# LED-Lampe_Power_ZXLD1362.net
KiCad netlist of a schematic drawn in EAGLE
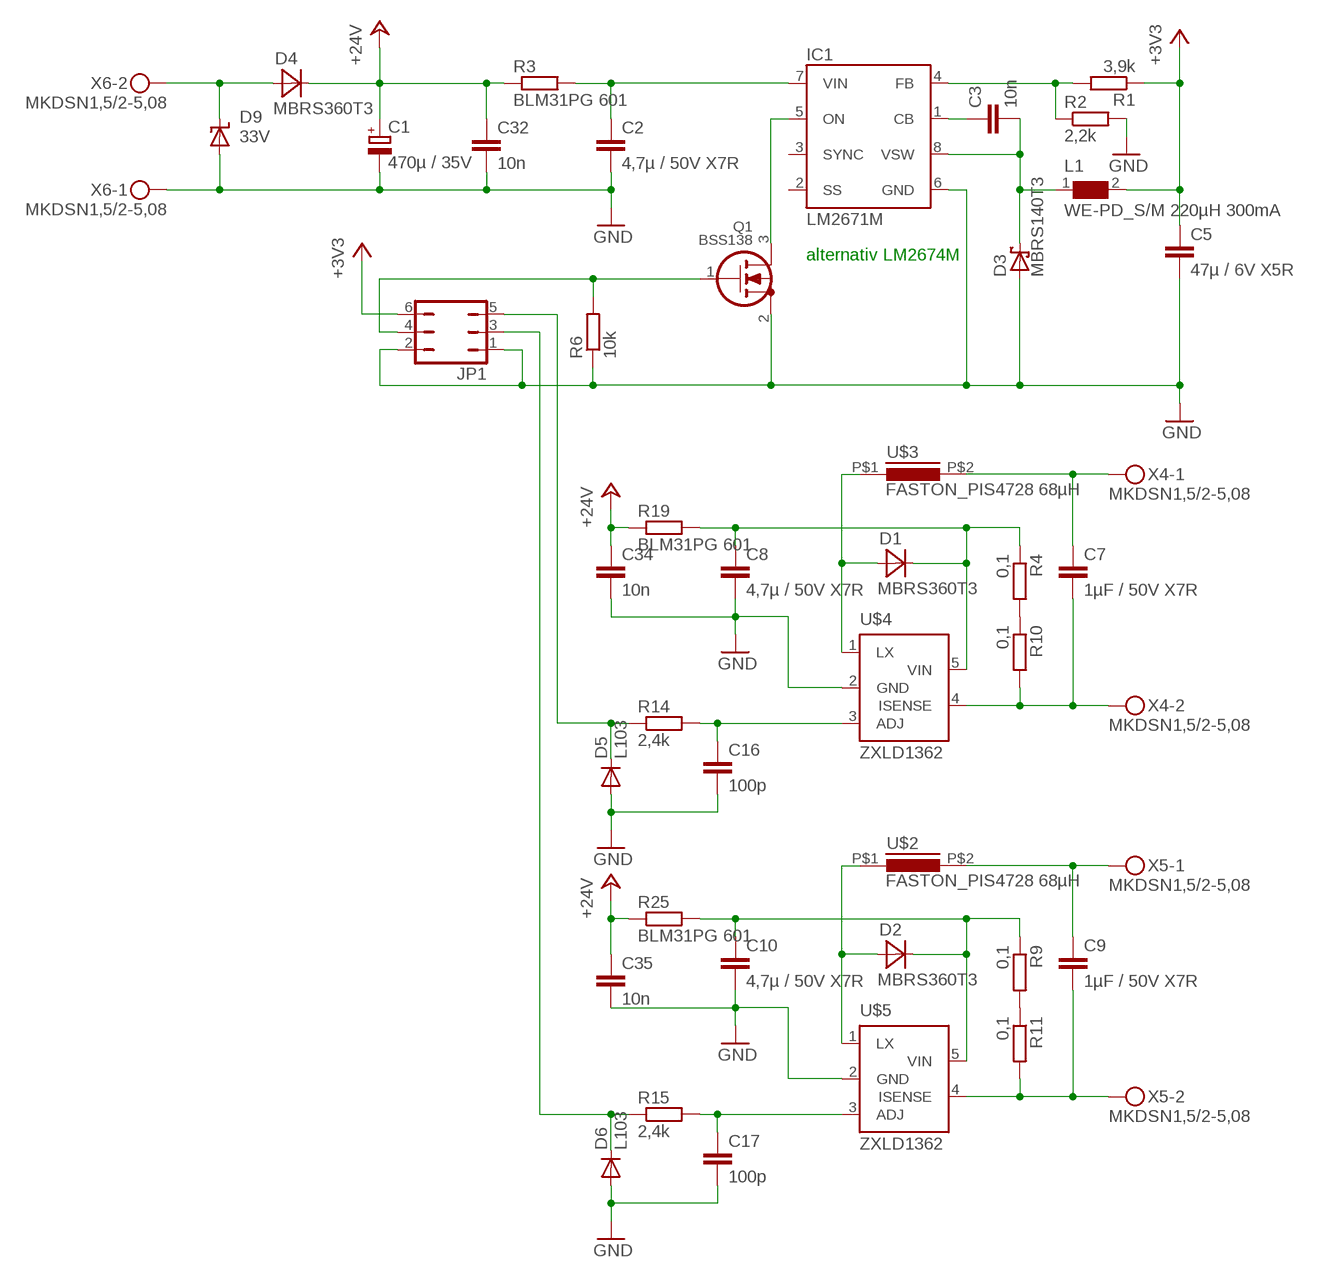
[diagram p0: schematic, sheet 1]

(export (version "E")
  (design (tool "Eeschema 10.0.6"))
  (components
    (comp (ref "C1")
      (value "470µ / 35V")
      (footprint "eagle-import:E5-13")
      (libsource (lib "eagle-import") (part "CPOL-EUE5-13"))
    )
    (comp (ref "C2")
      (value "4,7µ / 50V X7R")
      (footprint "eagle-import:C1206")
      (libsource (lib "eagle-import") (part "resistor_C-EUC1206"))
    )
    (comp (ref "C3")
      (value "10n")
      (footprint "eagle-import:C1206")
      (libsource (lib "eagle-import") (part "C-EUC1206"))
    )
    (comp (ref "C5")
      (value "47µ / 6V X5R")
      (footprint "eagle-import:C1206")
      (libsource (lib "eagle-import") (part "resistor_C-EUC1206"))
    )
    (comp (ref "C7")
      (value "1µF / 50V X7R")
      (footprint "eagle-import:C1206")
      (libsource (lib "eagle-import") (part "resistor_C-EUC1206"))
    )
    (comp (ref "C8")
      (value "4,7µ / 50V X7R")
      (footprint "eagle-import:C1206")
      (libsource (lib "eagle-import") (part "resistor_C-EUC1206"))
    )
    (comp (ref "C9")
      (value "1µF / 50V X7R")
      (footprint "eagle-import:C1206")
      (libsource (lib "eagle-import") (part "resistor_C-EUC1206"))
    )
    (comp (ref "C10")
      (value "4,7µ / 50V X7R")
      (footprint "eagle-import:C1206")
      (libsource (lib "eagle-import") (part "resistor_C-EUC1206"))
    )
    (comp (ref "C16")
      (value "100p")
      (footprint "eagle-import:C0603")
      (libsource (lib "eagle-import") (part "C-EUC0603"))
    )
    (comp (ref "C17")
      (value "100p")
      (footprint "eagle-import:C0603")
      (libsource (lib "eagle-import") (part "C-EUC0603"))
    )
    (comp (ref "C32")
      (value "10n")
      (footprint "eagle-import:C1206")
      (libsource (lib "eagle-import") (part "C-EUC1206"))
    )
    (comp (ref "C34")
      (value "10n")
      (footprint "eagle-import:C1206")
      (libsource (lib "eagle-import") (part "C-EUC1206"))
    )
    (comp (ref "C35")
      (value "10n")
      (footprint "eagle-import:C1206")
      (libsource (lib "eagle-import") (part "C-EUC1206"))
    )
    (comp (ref "D1")
      (value "MBRS360T3")
      (footprint "eagle-import:SMC")
      (libsource (lib "eagle-import") (part "MBRS360T3"))
    )
    (comp (ref "D2")
      (value "MBRS360T3")
      (footprint "eagle-import:SMC")
      (libsource (lib "eagle-import") (part "MBRS360T3"))
    )
    (comp (ref "D3")
      (value "MBRS140T3")
      (footprint "eagle-import:SMB")
      (libsource (lib "eagle-import") (part "SCHOTTKY-DIODESMD"))
    )
    (comp (ref "D4")
      (value "MBRS360T3")
      (footprint "eagle-import:SMC")
      (libsource (lib "eagle-import") (part "MBRS360T3"))
    )
    (comp (ref "D5")
      (value "L103")
      (footprint "eagle-import:SOD123")
      (libsource (lib "eagle-import") (part "DIODE-SOD123"))
    )
    (comp (ref "D6")
      (value "L103")
      (footprint "eagle-import:SOD123")
      (libsource (lib "eagle-import") (part "DIODE-SOD123"))
    )
    (comp (ref "D9")
      (value "33V")
      (footprint "eagle-import:SMBJ")
      (libsource (lib "eagle-import") (part "SUPPRESSOR-SMBJ"))
    )
    (comp (ref "IC1")
      (value "LM2671M")
      (footprint "eagle-import:SO08")
      (libsource (lib "eagle-import") (part "LM2671M"))
    )
    (comp (ref "JP1")
      (value "JP3Q")
      (footprint "eagle-import:JP3Q")
      (libsource (lib "eagle-import") (part "JP3Q"))
    )
    (comp (ref "L1")
      (value "WE-PD_S/M 220µH 300mA")
      (footprint "eagle-import:WE-PD_S_M")
      (libsource (lib "eagle-import") (part "WE-PD_S/M"))
    )
    (comp (ref "Q1")
      (value "BSS138")
      (footprint "eagle-import:SOT23")
      (libsource (lib "eagle-import") (part "BSS138"))
    )
    (comp (ref "R1")
      (value "3,9k")
      (footprint "eagle-import:R1206")
      (libsource (lib "eagle-import") (part "R-EU_R1206"))
    )
    (comp (ref "R2")
      (value "2,2k")
      (footprint "eagle-import:R1206")
      (libsource (lib "eagle-import") (part "R-EU_R1206"))
    )
    (comp (ref "R3")
      (value "BLM31PG 601")
      (footprint "eagle-import:R1206@1")
      (libsource (lib "eagle-import") (part "resistor_R-EU_R1206"))
    )
    (comp (ref "R4")
      (value "0,1")
      (footprint "eagle-import:R1206@1")
      (libsource (lib "eagle-import") (part "resistor_R-EU_R1206"))
    )
    (comp (ref "R6")
      (value "10k")
      (footprint "eagle-import:R1206")
      (libsource (lib "eagle-import") (part "R-EU_R1206"))
    )
    (comp (ref "R9")
      (value "0,1")
      (footprint "eagle-import:R1206@1")
      (libsource (lib "eagle-import") (part "resistor_R-EU_R1206"))
    )
    (comp (ref "R10")
      (value "0,1")
      (footprint "eagle-import:R1206@1")
      (libsource (lib "eagle-import") (part "resistor_R-EU_R1206"))
    )
    (comp (ref "R11")
      (value "0,1")
      (footprint "eagle-import:R1206@1")
      (libsource (lib "eagle-import") (part "resistor_R-EU_R1206"))
    )
    (comp (ref "R14")
      (value "2,4k")
      (footprint "eagle-import:R1206")
      (libsource (lib "eagle-import") (part "R-EU_R1206"))
    )
    (comp (ref "R15")
      (value "2,4k")
      (footprint "eagle-import:R1206")
      (libsource (lib "eagle-import") (part "R-EU_R1206"))
    )
    (comp (ref "R19")
      (value "BLM31PG 601")
      (footprint "eagle-import:R1206@1")
      (libsource (lib "eagle-import") (part "resistor_R-EU_R1206"))
    )
    (comp (ref "R25")
      (value "BLM31PG 601")
      (footprint "eagle-import:R1206@1")
      (libsource (lib "eagle-import") (part "resistor_R-EU_R1206"))
    )
    (comp (ref "U$2")
      (value "FASTON_PIS4728 68µH")
      (footprint "eagle-import:FASTON_PIS4728")
      (libsource (lib "eagle-import") (part "FASTON_PIS4728"))
    )
    (comp (ref "U$3")
      (value "FASTON_PIS4728 68µH")
      (footprint "eagle-import:FASTON_PIS4728")
      (libsource (lib "eagle-import") (part "FASTON_PIS4728"))
    )
    (comp (ref "U$4")
      (value "ZXLD1362")
      (footprint "eagle-import:SOT23-5")
      (libsource (lib "eagle-import") (part "ZXLD1362"))
    )
    (comp (ref "U$5")
      (value "ZXLD1362")
      (footprint "eagle-import:SOT23-5")
      (libsource (lib "eagle-import") (part "ZXLD1362"))
    )
    (comp (ref "X4")
      (value "MKDSN1,5/2-5,08")
      (footprint "eagle-import:MKDSN1,5_2-5,08")
      (fields (field (name "MPN") "MKDSN 1,5/2-5.08"))
      (libsource (lib "eagle-import") (part "MKDSN1,5/2-5,08"))
    )
    (comp (ref "X5")
      (value "MKDSN1,5/2-5,08")
      (footprint "eagle-import:MKDSN1,5_2-5,08")
      (fields (field (name "MPN") "MKDSN 1,5/2-5.08"))
      (libsource (lib "eagle-import") (part "MKDSN1,5/2-5,08"))
    )
    (comp (ref "X6")
      (value "MKDSN1,5/2-5,08")
      (footprint "eagle-import:MKDSN1,5_2-5,08")
      (fields (field (name "MPN") "MKDSN 1,5/2-5.08"))
      (libsource (lib "eagle-import") (part "MKDSN1,5/2-5,08"))
    )
  )
  (nets
    (net (code "1") (name "+3V3") (class "Default")
      (node (ref "C5") (pin "1") (pinfunction "1_1") (pintype "passive"))
      (node (ref "JP1") (pin "6") (pinfunction "6_6") (pintype "passive"))
      (node (ref "L1") (pin "2") (pinfunction "2_2") (pintype "passive"))
      (node (ref "R1") (pin "1") (pinfunction "1_1") (pintype "passive"))
    )
    (net (code "2") (name "+24V") (class "Default")
      (node (ref "C1") (pin "+") (pinfunction "+_+") (pintype "passive"))
      (node (ref "C32") (pin "1") (pinfunction "1_1") (pintype "passive"))
      (node (ref "C34") (pin "1") (pinfunction "1_1") (pintype "passive"))
      (node (ref "C35") (pin "1") (pinfunction "1_1") (pintype "passive"))
      (node (ref "D4") (pin "C") (pinfunction "C_C") (pintype "passive"))
      (node (ref "R19") (pin "1") (pinfunction "1_1") (pintype "passive"))
      (node (ref "R25") (pin "1") (pinfunction "1_1") (pintype "passive"))
      (node (ref "R3") (pin "1") (pinfunction "1_1") (pintype "passive"))
    )
    (net (code "3") (name "GND") (class "Default")
      (node (ref "C1") (pin "-") (pinfunction "-_-") (pintype "passive"))
      (node (ref "C10") (pin "2") (pinfunction "2_2") (pintype "passive"))
      (node (ref "C16") (pin "2") (pinfunction "2_2") (pintype "passive"))
      (node (ref "C17") (pin "2") (pinfunction "2_2") (pintype "passive"))
      (node (ref "C2") (pin "2") (pinfunction "2_2") (pintype "passive"))
      (node (ref "C32") (pin "2") (pinfunction "2_2") (pintype "passive"))
      (node (ref "C34") (pin "2") (pinfunction "2_2") (pintype "passive"))
      (node (ref "C35") (pin "2") (pinfunction "2_2") (pintype "passive"))
      (node (ref "C5") (pin "2") (pinfunction "2_2") (pintype "passive"))
      (node (ref "C8") (pin "2") (pinfunction "2_2") (pintype "passive"))
      (node (ref "D3") (pin "A") (pinfunction "A_A") (pintype "passive"))
      (node (ref "D5") (pin "A") (pinfunction "A_A") (pintype "passive"))
      (node (ref "D6") (pin "A") (pinfunction "A_A") (pintype "passive"))
      (node (ref "D9") (pin "A") (pinfunction "A_A") (pintype "passive"))
      (node (ref "IC1") (pin "6") (pinfunction "GND_6") (pintype "power_in"))
      (node (ref "JP1") (pin "1") (pinfunction "1_1") (pintype "passive"))
      (node (ref "JP1") (pin "2") (pinfunction "2_2") (pintype "passive"))
      (node (ref "Q1") (pin "2") (pinfunction "S_2") (pintype "bidirectional"))
      (node (ref "R2") (pin "2") (pinfunction "2_2") (pintype "passive"))
      (node (ref "R6") (pin "1") (pinfunction "1_1") (pintype "passive"))
      (node (ref "U$4") (pin "2") (pinfunction "GND_2") (pintype "power_in"))
      (node (ref "U$5") (pin "2") (pinfunction "GND_2") (pintype "power_in"))
      (node (ref "X6") (pin "1") (pinfunction "KL_1") (pintype "passive"))
    )
    (net (code "4") (name "Net-(D5-PadC)") (class "Default")
      (node (ref "D5") (pin "C") (pinfunction "C_C") (pintype "passive"))
      (node (ref "JP1") (pin "5") (pinfunction "5_5") (pintype "passive"))
      (node (ref "R14") (pin "1") (pinfunction "1_1") (pintype "passive"))
    )
    (net (code "5") (name "Net-(D6-PadC)") (class "Default")
      (node (ref "D6") (pin "C") (pinfunction "C_C") (pintype "passive"))
      (node (ref "JP1") (pin "3") (pinfunction "3_3") (pintype "passive"))
      (node (ref "R15") (pin "1") (pinfunction "1_1") (pintype "passive"))
    )
    (net (code "6") (name "Net-(IC1-CB)") (class "Default")
      (node (ref "C3") (pin "1") (pinfunction "1_1") (pintype "passive"))
      (node (ref "IC1") (pin "1") (pinfunction "CB_1") (pintype "input"))
    )
    (net (code "7") (name "Net-(IC1-FB)") (class "Default")
      (node (ref "IC1") (pin "4") (pinfunction "FB_4") (pintype "input"))
      (node (ref "R1") (pin "2") (pinfunction "2_2") (pintype "passive"))
      (node (ref "R2") (pin "1") (pinfunction "1_1") (pintype "passive"))
    )
    (net (code "8") (name "Net-(IC1-ON)") (class "Default")
      (node (ref "IC1") (pin "5") (pinfunction "ON_5") (pintype "passive"))
      (node (ref "Q1") (pin "3") (pinfunction "D_3") (pintype "bidirectional"))
    )
    (net (code "9") (name "Net-(IC1-VIN)") (class "Default")
      (node (ref "C2") (pin "1") (pinfunction "1_1") (pintype "passive"))
      (node (ref "IC1") (pin "7") (pinfunction "VIN_7") (pintype "power_in"))
      (node (ref "R3") (pin "2") (pinfunction "2_2") (pintype "passive"))
    )
    (net (code "10") (name "Net-(IC1-VSW)") (class "Default")
      (node (ref "C3") (pin "2") (pinfunction "2_2") (pintype "passive"))
      (node (ref "D3") (pin "C") (pinfunction "C_C") (pintype "passive"))
      (node (ref "IC1") (pin "8") (pinfunction "VSW_8") (pintype "output"))
      (node (ref "L1") (pin "1") (pinfunction "1_1") (pintype "passive"))
    )
    (net (code "11") (name "Net-(Q1-G)") (class "Default")
      (node (ref "JP1") (pin "4") (pinfunction "4_4") (pintype "passive"))
      (node (ref "Q1") (pin "1") (pinfunction "G_1") (pintype "bidirectional"))
      (node (ref "R6") (pin "2") (pinfunction "2_2") (pintype "passive"))
    )
    (net (code "12") (name "Net-(R10-Pad1)") (class "Default")
      (node (ref "R10") (pin "1") (pinfunction "1_1") (pintype "passive"))
      (node (ref "R4") (pin "2") (pinfunction "2_2") (pintype "passive"))
    )
    (net (code "13") (name "Net-(R11-Pad1)") (class "Default")
      (node (ref "R11") (pin "1") (pinfunction "1_1") (pintype "passive"))
      (node (ref "R9") (pin "2") (pinfunction "2_2") (pintype "passive"))
    )
    (net (code "14") (name "Net-(U$2-1)") (class "Default")
      (node (ref "D2") (pin "A") (pinfunction "A_A") (pintype "passive"))
      (node (ref "U$2") (pin "P$1") (pinfunction "1_P$1") (pintype "passive"))
      (node (ref "U$5") (pin "1") (pinfunction "LX_1") (pintype "output"))
    )
    (net (code "15") (name "Net-(U$2-2)") (class "Default")
      (node (ref "C9") (pin "1") (pinfunction "1_1") (pintype "passive"))
      (node (ref "U$2") (pin "P$2") (pinfunction "2_P$2") (pintype "passive"))
      (node (ref "X5") (pin "1") (pinfunction "KL_1") (pintype "passive"))
    )
    (net (code "16") (name "Net-(U$3-1)") (class "Default")
      (node (ref "D1") (pin "A") (pinfunction "A_A") (pintype "passive"))
      (node (ref "U$3") (pin "P$1") (pinfunction "1_P$1") (pintype "passive"))
      (node (ref "U$4") (pin "1") (pinfunction "LX_1") (pintype "output"))
    )
    (net (code "17") (name "Net-(U$3-2)") (class "Default")
      (node (ref "C7") (pin "1") (pinfunction "1_1") (pintype "passive"))
      (node (ref "U$3") (pin "P$2") (pinfunction "2_P$2") (pintype "passive"))
      (node (ref "X4") (pin "1") (pinfunction "KL_1") (pintype "passive"))
    )
    (net (code "18") (name "Net-(U$4-ADJ)") (class "Default")
      (node (ref "C16") (pin "1") (pinfunction "1_1") (pintype "passive"))
      (node (ref "R14") (pin "2") (pinfunction "2_2") (pintype "passive"))
      (node (ref "U$4") (pin "3") (pinfunction "ADJ_3") (pintype "input"))
    )
    (net (code "19") (name "Net-(U$4-ISENSE)") (class "Default")
      (node (ref "C7") (pin "2") (pinfunction "2_2") (pintype "passive"))
      (node (ref "R10") (pin "2") (pinfunction "2_2") (pintype "passive"))
      (node (ref "U$4") (pin "4") (pinfunction "ISENSE_4") (pintype "input"))
      (node (ref "X4") (pin "2") (pinfunction "KL_2") (pintype "passive"))
    )
    (net (code "20") (name "Net-(U$4-VIN)") (class "Default")
      (node (ref "C8") (pin "1") (pinfunction "1_1") (pintype "passive"))
      (node (ref "D1") (pin "C") (pinfunction "C_C") (pintype "passive"))
      (node (ref "R19") (pin "2") (pinfunction "2_2") (pintype "passive"))
      (node (ref "R4") (pin "1") (pinfunction "1_1") (pintype "passive"))
      (node (ref "U$4") (pin "5") (pinfunction "VIN_5") (pintype "power_in"))
    )
    (net (code "21") (name "Net-(U$5-ADJ)") (class "Default")
      (node (ref "C17") (pin "1") (pinfunction "1_1") (pintype "passive"))
      (node (ref "R15") (pin "2") (pinfunction "2_2") (pintype "passive"))
      (node (ref "U$5") (pin "3") (pinfunction "ADJ_3") (pintype "input"))
    )
    (net (code "22") (name "Net-(U$5-ISENSE)") (class "Default")
      (node (ref "C9") (pin "2") (pinfunction "2_2") (pintype "passive"))
      (node (ref "R11") (pin "2") (pinfunction "2_2") (pintype "passive"))
      (node (ref "U$5") (pin "4") (pinfunction "ISENSE_4") (pintype "input"))
      (node (ref "X5") (pin "2") (pinfunction "KL_2") (pintype "passive"))
    )
    (net (code "23") (name "Net-(U$5-VIN)") (class "Default")
      (node (ref "C10") (pin "1") (pinfunction "1_1") (pintype "passive"))
      (node (ref "D2") (pin "C") (pinfunction "C_C") (pintype "passive"))
      (node (ref "R25") (pin "2") (pinfunction "2_2") (pintype "passive"))
      (node (ref "R9") (pin "1") (pinfunction "1_1") (pintype "passive"))
      (node (ref "U$5") (pin "5") (pinfunction "VIN_5") (pintype "power_in"))
    )
    (net (code "24") (name "Net-(X6B-KL)") (class "Default")
      (node (ref "D4") (pin "A") (pinfunction "A_A") (pintype "passive"))
      (node (ref "D9") (pin "C") (pinfunction "C_C") (pintype "passive"))
      (node (ref "X6") (pin "2") (pinfunction "KL_2") (pintype "passive"))
    )
    (net (code "25") (name "unconnected-(IC1-SS-Pad2)") (class "Default")
      (node (ref "IC1") (pin "2") (pinfunction "SS_2") (pintype "passive"))
    )
    (net (code "26") (name "unconnected-(IC1-SYNC-Pad3)") (class "Default")
      (node (ref "IC1") (pin "3") (pinfunction "SYNC_3") (pintype "passive"))
    )
  )
)
